# mister_patch.net
KiCad netlist of a schematic drawn in EAGLE
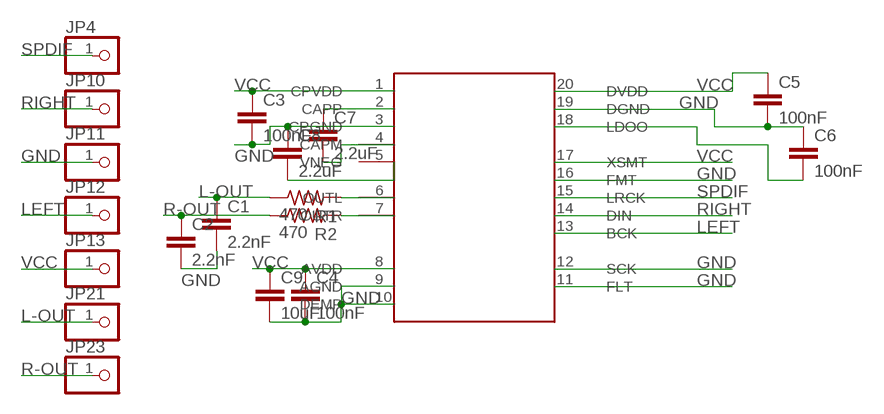
[diagram p0: schematic, sheet 1]

(export (version "E")
  (design (tool "Eeschema 10.0.6"))
  (components
    (comp (ref "C1")
      (value "2.2nF")
      (footprint "eagle-import:C0603K")
      (libsource (lib "eagle-import") (part "C-EUC0603K"))
    )
    (comp (ref "C2")
      (value "2.2nF")
      (footprint "eagle-import:C0603K")
      (libsource (lib "eagle-import") (part "C-EUC0603K"))
    )
    (comp (ref "C3")
      (value "100nF")
      (footprint "eagle-import:C0603K")
      (libsource (lib "eagle-import") (part "C-EUC0603K"))
    )
    (comp (ref "C4")
      (value "100nF")
      (footprint "eagle-import:C0603K")
      (libsource (lib "eagle-import") (part "C-EUC0603K"))
    )
    (comp (ref "C5")
      (value "100nF")
      (footprint "eagle-import:C0603K")
      (libsource (lib "eagle-import") (part "C-EUC0603K"))
    )
    (comp (ref "C6")
      (value "100nF")
      (footprint "eagle-import:C0603K")
      (libsource (lib "eagle-import") (part "C-EUC0603K"))
    )
    (comp (ref "C7")
      (value "2.2uF")
      (footprint "eagle-import:C0603K")
      (libsource (lib "eagle-import") (part "C-EUC0603K"))
    )
    (comp (ref "C8")
      (value "2.2uF")
      (footprint "eagle-import:C0603K")
      (libsource (lib "eagle-import") (part "C-EUC0603K"))
    )
    (comp (ref "C9")
      (value "10uF")
      (footprint "eagle-import:C0603K")
      (libsource (lib "eagle-import") (part "C-EUC0603K"))
    )
    (comp (ref "JP4")
      (value "PINHD-1X1")
      (footprint "eagle-import:1X01")
      (libsource (lib "eagle-import") (part "PINHD-1X1"))
    )
    (comp (ref "JP10")
      (value "PINHD-1X1")
      (footprint "eagle-import:1X01")
      (libsource (lib "eagle-import") (part "PINHD-1X1"))
    )
    (comp (ref "JP11")
      (value "PINHD-1X1")
      (footprint "eagle-import:1X01")
      (libsource (lib "eagle-import") (part "PINHD-1X1"))
    )
    (comp (ref "JP12")
      (value "PINHD-1X1")
      (footprint "eagle-import:1X01")
      (libsource (lib "eagle-import") (part "PINHD-1X1"))
    )
    (comp (ref "JP13")
      (value "PINHD-1X1")
      (footprint "eagle-import:1X01")
      (libsource (lib "eagle-import") (part "PINHD-1X1"))
    )
    (comp (ref "JP21")
      (value "PINHD-1X1")
      (footprint "eagle-import:1X01")
      (libsource (lib "eagle-import") (part "PINHD-1X1"))
    )
    (comp (ref "JP23")
      (value "PINHD-1X1")
      (footprint "eagle-import:1X01")
      (libsource (lib "eagle-import") (part "PINHD-1X1"))
    )
    (comp (ref "R1")
      (value "470")
      (footprint "eagle-import:R0603")
      (libsource (lib "eagle-import") (part "R-US_R0603"))
    )
    (comp (ref "R2")
      (value "470")
      (footprint "eagle-import:R0603")
      (libsource (lib "eagle-import") (part "R-US_R0603"))
    )
    (comp (ref "U$1")
      (value "PCM5102")
      (footprint "eagle-import:TSSOP20")
      (libsource (lib "eagle-import") (part "PCM5102"))
    )
  )
  (nets
    (net (code "1") (name "/GND") (class "Default")
      (node (ref "C1") (pin "2") (pinfunction "2_2") (pintype "passive"))
      (node (ref "C2") (pin "2") (pinfunction "2_2") (pintype "passive"))
      (node (ref "C3") (pin "2") (pinfunction "2_2") (pintype "passive"))
      (node (ref "C4") (pin "2") (pinfunction "2_2") (pintype "passive"))
      (node (ref "C5") (pin "2") (pinfunction "2_2") (pintype "passive"))
      (node (ref "C6") (pin "1") (pinfunction "1_1") (pintype "passive"))
      (node (ref "C8") (pin "1") (pinfunction "1_1") (pintype "passive"))
      (node (ref "C9") (pin "2") (pinfunction "2_2") (pintype "passive"))
      (node (ref "JP11") (pin "1") (pinfunction "1_1") (pintype "passive"))
      (node (ref "U$1") (pin "10") (pinfunction "DEMP_10") (pintype "bidirectional"))
      (node (ref "U$1") (pin "11") (pinfunction "FLT_11") (pintype "bidirectional"))
      (node (ref "U$1") (pin "12") (pinfunction "SCK_12") (pintype "bidirectional"))
      (node (ref "U$1") (pin "16") (pinfunction "FMT_16") (pintype "bidirectional"))
      (node (ref "U$1") (pin "19") (pinfunction "DGND_19") (pintype "bidirectional"))
      (node (ref "U$1") (pin "3") (pinfunction "CPGND_3") (pintype "bidirectional"))
      (node (ref "U$1") (pin "9") (pinfunction "AGND_9") (pintype "bidirectional"))
    )
    (net (code "2") (name "/L-OUT") (class "Default")
      (node (ref "C1") (pin "1") (pinfunction "1_1") (pintype "passive"))
      (node (ref "JP21") (pin "1") (pinfunction "1_1") (pintype "passive"))
      (node (ref "R1") (pin "1") (pinfunction "1_1") (pintype "passive"))
    )
    (net (code "3") (name "/LEFT") (class "Default")
      (node (ref "JP12") (pin "1") (pinfunction "1_1") (pintype "passive"))
      (node (ref "U$1") (pin "13") (pinfunction "BCK_13") (pintype "bidirectional"))
    )
    (net (code "4") (name "/R-OUT") (class "Default")
      (node (ref "C2") (pin "1") (pinfunction "1_1") (pintype "passive"))
      (node (ref "JP23") (pin "1") (pinfunction "1_1") (pintype "passive"))
      (node (ref "R2") (pin "1") (pinfunction "1_1") (pintype "passive"))
    )
    (net (code "5") (name "/RIGHT") (class "Default")
      (node (ref "JP10") (pin "1") (pinfunction "1_1") (pintype "passive"))
      (node (ref "U$1") (pin "14") (pinfunction "DIN_14") (pintype "bidirectional"))
    )
    (net (code "6") (name "/SPDIF") (class "Default")
      (node (ref "JP4") (pin "1") (pinfunction "1_1") (pintype "passive"))
      (node (ref "U$1") (pin "15") (pinfunction "LRCK_15") (pintype "bidirectional"))
    )
    (net (code "7") (name "/VCC") (class "Default")
      (node (ref "C3") (pin "1") (pinfunction "1_1") (pintype "passive"))
      (node (ref "C4") (pin "1") (pinfunction "1_1") (pintype "passive"))
      (node (ref "C5") (pin "1") (pinfunction "1_1") (pintype "passive"))
      (node (ref "C9") (pin "1") (pinfunction "1_1") (pintype "passive"))
      (node (ref "JP13") (pin "1") (pinfunction "1_1") (pintype "passive"))
      (node (ref "U$1") (pin "1") (pinfunction "CPVDD_1") (pintype "bidirectional"))
      (node (ref "U$1") (pin "17") (pinfunction "XSMT_17") (pintype "bidirectional"))
      (node (ref "U$1") (pin "20") (pinfunction "DVDD_20") (pintype "bidirectional"))
      (node (ref "U$1") (pin "8") (pinfunction "AVDD_8") (pintype "bidirectional"))
    )
    (net (code "8") (name "Net-(U$1-CAPM)") (class "Default")
      (node (ref "C7") (pin "2") (pinfunction "2_2") (pintype "passive"))
      (node (ref "U$1") (pin "4") (pinfunction "CAPM_4") (pintype "bidirectional"))
    )
    (net (code "9") (name "Net-(U$1-CAPP)") (class "Default")
      (node (ref "C7") (pin "1") (pinfunction "1_1") (pintype "passive"))
      (node (ref "U$1") (pin "2") (pinfunction "CAPP_2") (pintype "bidirectional"))
    )
    (net (code "10") (name "Net-(U$1-LDOO)") (class "Default")
      (node (ref "C6") (pin "2") (pinfunction "2_2") (pintype "passive"))
      (node (ref "U$1") (pin "18") (pinfunction "LDOO_18") (pintype "bidirectional"))
    )
    (net (code "11") (name "Net-(U$1-OUTL)") (class "Default")
      (node (ref "R1") (pin "2") (pinfunction "2_2") (pintype "passive"))
      (node (ref "U$1") (pin "6") (pinfunction "OUTL_6") (pintype "bidirectional"))
    )
    (net (code "12") (name "Net-(U$1-OUTR)") (class "Default")
      (node (ref "R2") (pin "2") (pinfunction "2_2") (pintype "passive"))
      (node (ref "U$1") (pin "7") (pinfunction "OUTR_7") (pintype "bidirectional"))
    )
    (net (code "13") (name "Net-(U$1-VNEG)") (class "Default")
      (node (ref "C8") (pin "2") (pinfunction "2_2") (pintype "passive"))
      (node (ref "U$1") (pin "5") (pinfunction "VNEG_5") (pintype "bidirectional"))
    )
  )
)
